# AVRKernel.net
KiCad netlist of a schematic drawn in Altium Designer
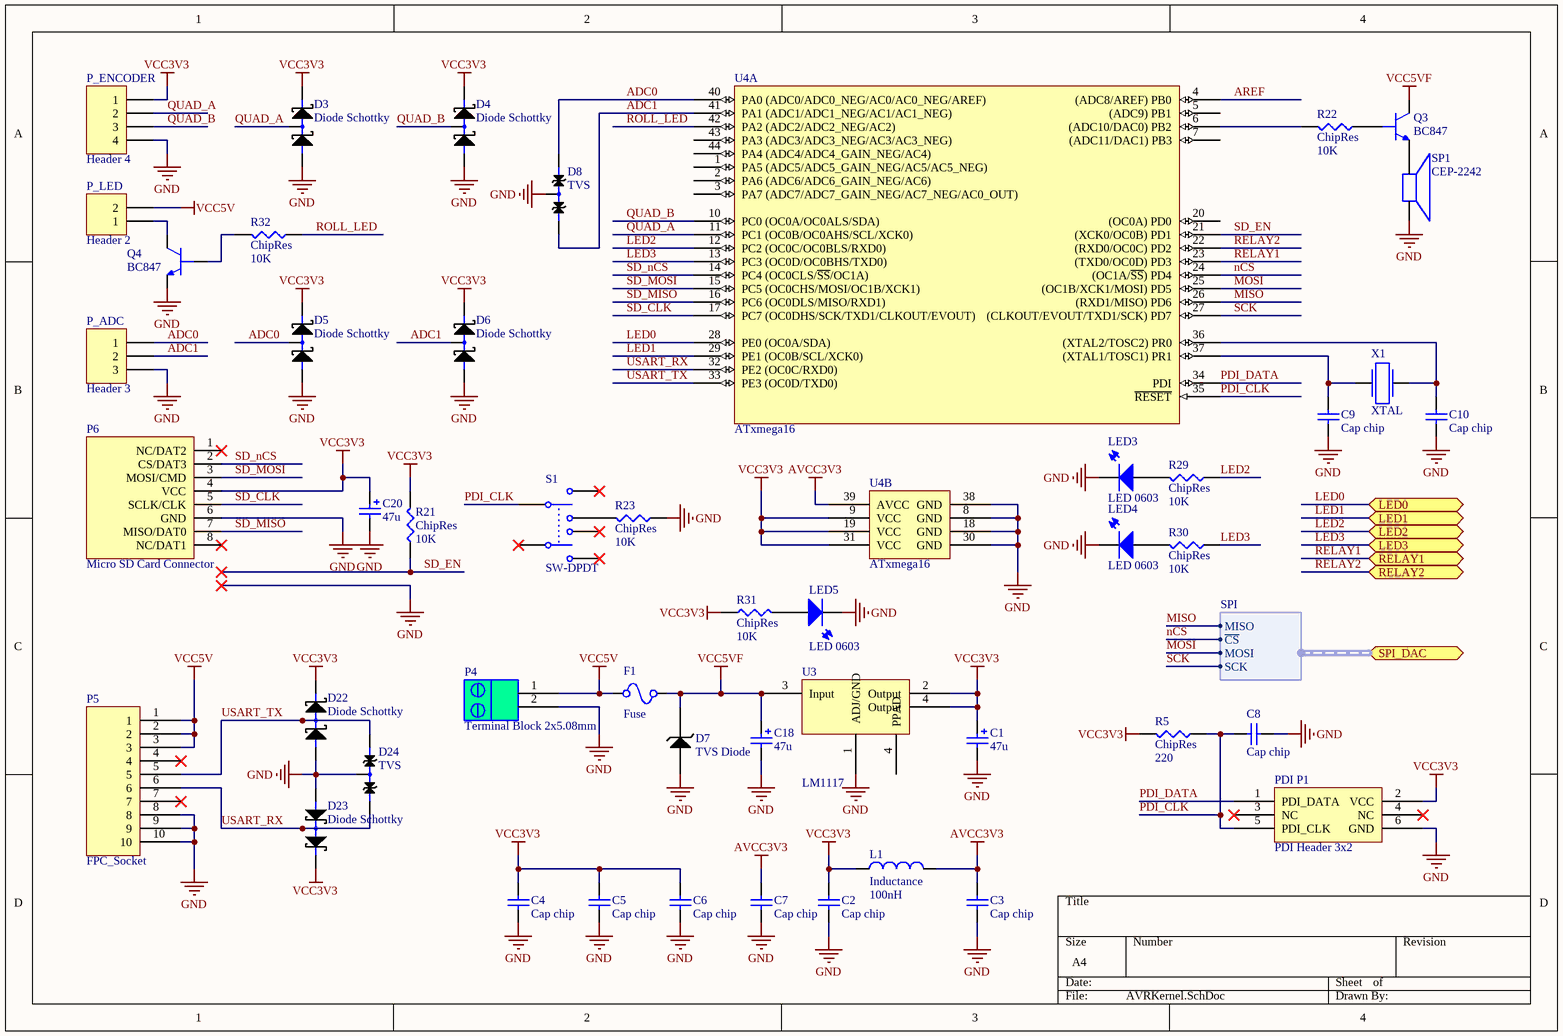
[diagram p0: AVRKernel.SchDoc]

(export (version "E")
  (design (tool "Eeschema 10.0.6"))
  (components
    (comp (ref "C1")
      (value "47u")
      (footprint "CAPC7343")
      (description "Polarized Capacitor (Radial)")
      (fields (field (name "Comment") "Cap Pol SMD"))
      (libsource (lib "Common Devices") (part "Cap Pol Chip"))
    )
    (comp (ref "C2")
      (value "Cap chip")
      (footprint "CAPC3216")
      (description "Chip Capacitor")
      (fields (field (name "PUBLISHER") "Altium Limited"))
      (libsource (lib "Common Devices") (part "Cap chip"))
    )
    (comp (ref "C3")
      (value "Cap chip")
      (footprint "CAPC3216")
      (description "Chip Capacitor")
      (fields (field (name "PUBLISHER") "Altium Limited"))
      (libsource (lib "Common Devices") (part "Cap chip"))
    )
    (comp (ref "C4")
      (value "Cap chip")
      (footprint "CAPC3216")
      (description "Chip Capacitor")
      (fields (field (name "PUBLISHER") "Altium Limited"))
      (libsource (lib "Common Devices") (part "Cap chip"))
    )
    (comp (ref "C5")
      (value "Cap chip")
      (footprint "CAPC3216")
      (description "Chip Capacitor")
      (fields (field (name "PUBLISHER") "Altium Limited"))
      (libsource (lib "Common Devices") (part "Cap chip"))
    )
    (comp (ref "C6")
      (value "Cap chip")
      (footprint "CAPC3216")
      (description "Chip Capacitor")
      (fields (field (name "PUBLISHER") "Altium Limited"))
      (libsource (lib "Common Devices") (part "Cap chip"))
    )
    (comp (ref "C7")
      (value "Cap chip")
      (footprint "CAPC3216")
      (description "Chip Capacitor")
      (fields (field (name "PUBLISHER") "Altium Limited"))
      (libsource (lib "Common Devices") (part "Cap chip"))
    )
    (comp (ref "C8")
      (value "Cap chip")
      (footprint "CAPC3216")
      (description "Chip Capacitor")
      (fields (field (name "PUBLISHER") "Altium Limited"))
      (libsource (lib "Common Devices") (part "Cap chip"))
    )
    (comp (ref "C9")
      (value "Cap chip")
      (footprint "CAPC3216")
      (description "Chip Capacitor")
      (fields (field (name "PUBLISHER") "Altium Limited"))
      (libsource (lib "Common Devices") (part "Cap chip"))
    )
    (comp (ref "C10")
      (value "Cap chip")
      (footprint "CAPC3216")
      (description "Chip Capacitor")
      (fields (field (name "PUBLISHER") "Altium Limited"))
      (libsource (lib "Common Devices") (part "Cap chip"))
    )
    (comp (ref "C18")
      (value "47u")
      (footprint "CAPC7343")
      (description "Polarized Capacitor (Radial)")
      (fields (field (name "Comment") "Cap Pol SMD"))
      (libsource (lib "Common Devices") (part "Cap Pol Chip"))
    )
    (comp (ref "C20")
      (value "47u")
      (footprint "CAPC7343")
      (description "Polarized Capacitor (Radial)")
      (fields (field (name "Comment") "Cap Pol SMD"))
      (libsource (lib "Common Devices") (part "Cap Pol Chip"))
    )
    (comp (ref "D3")
      (value "Diode Schottky")
      (footprint "SOT23")
      (description "2-Diode Schottky")
      (libsource (lib "Protection") (part "Schottky Diode"))
    )
    (comp (ref "D4")
      (value "Diode Schottky")
      (footprint "SOT23")
      (description "2-Diode Schottky")
      (libsource (lib "Protection") (part "Schottky Diode"))
    )
    (comp (ref "D5")
      (value "Diode Schottky")
      (footprint "SOT23")
      (description "2-Diode Schottky")
      (libsource (lib "Protection") (part "Schottky Diode"))
    )
    (comp (ref "D6")
      (value "Diode Schottky")
      (footprint "SOT23")
      (description "2-Diode Schottky")
      (libsource (lib "Protection") (part "Schottky Diode"))
    )
    (comp (ref "D7")
      (value "TVS Diode")
      (footprint "DO-214AS")
      (libsource (lib "Protection") (part "TVS Diode SMA"))
    )
    (comp (ref "D8")
      (value "TVS")
      (footprint "SOT23")
      (description "Dual bidirectional voltage supresor")
      (libsource (lib "Protection") (part "TVS Diode"))
    )
    (comp (ref "D22")
      (value "Diode Schottky")
      (footprint "SOT23")
      (description "2-Diode Schottky")
      (libsource (lib "Protection") (part "Schottky Diode"))
    )
    (comp (ref "D23")
      (value "Diode Schottky")
      (footprint "SOT23")
      (description "2-Diode Schottky")
      (libsource (lib "") (part "Schottky Diode_1"))
    )
    (comp (ref "D24")
      (value "TVS")
      (footprint "SOT23")
      (description "Dual bidirectional voltage supresor")
      (libsource (lib "Protection") (part "TVS Diode"))
    )
    (comp (ref "F1")
      (value "Fuse")
      (footprint "PTC1812")
      (description "Fuse PTC 1812 Thermoresistor")
      (libsource (lib "Protection") (part "Fuse PTC1812"))
    )
    (comp (ref "L1")
      (value "Inductance")
      (footprint "CM45")
      (fields (field (name "ALTIUM_VALUE") "100nH"))
      (libsource (lib "Common Devices") (part "ChipInductance"))
    )
    (comp (ref "LED3") (value "LED 0603") (footprint "LED 0603") (libsource (lib "LEDs") (part "LED0603")))
    (comp (ref "LED4") (value "LED 0603") (footprint "LED 0603") (libsource (lib "LEDs") (part "LED0603")))
    (comp (ref "LED5") (value "LED 0603") (footprint "LED 0603") (libsource (lib "LEDs") (part "LED0603")))
    (comp (ref "P4")
      (value "Terminal Block 2x5.08mm")
      (footprint "Socket 2x5.08")
      (description "Terminal Block Socket Right Angle 2x5.08mm 2 Wall")
      (libsource (lib "IndustrialConnectors") (part "Socket_2x5.08_RA_2Wall"))
    )
    (comp (ref "P5")
      (value "FPC_Socket")
      (footprint "Molex FPC/FFC 10pin")
      (libsource (lib "RibbonConnector") (part "FPC_Socket"))
    )
    (comp (ref "P6")
      (value "Micro SD Card Connector")
      (footprint "WR-CRD SD Micro")
      (libsource (lib "Connectors") (part "MicroSDHeader8"))
    )
    (comp (ref "PDI P1")
      (value "PDI Header 3x2")
      (footprint "Header 3x2")
      (description "PDI Interface connector")
      (libsource (lib "IndustrialConnectors") (part "PDI Header 3x2"))
    )
    (comp (ref "P_ADC")
      (value "Header 3")
      (footprint "HDR1X3")
      (description "Header, 3-Pin")
      (fields (field (name "PUBLISHER") "Altium Limited"))
      (libsource (lib "Miscellaneous Connectors") (part "Header 3"))
    )
    (comp (ref "P_ENCODER")
      (value "Header 4")
      (footprint "HDR1X4")
      (description "Header, 4-Pin")
      (fields (field (name "PUBLISHER") "Altium Limited"))
      (libsource (lib "Miscellaneous Connectors") (part "Header 4"))
    )
    (comp (ref "P_LED")
      (value "Header 2")
      (footprint "HDR1X2")
      (description "Header, 2-Pin")
      (fields (field (name "PUBLISHER") "Altium Limited"))
      (libsource (lib "Miscellaneous Connectors") (part "Header 2"))
    )
    (comp (ref "Q3")
      (value "BC847")
      (footprint "SOT23")
      (description "NPN transistor")
      (libsource (lib "BJT") (part "BC847"))
    )
    (comp (ref "Q4")
      (value "BC847")
      (footprint "SOT23")
      (description "NPN transistor")
      (libsource (lib "BJT") (part "BC847"))
    )
    (comp (ref "R5")
      (value "ChipRes")
      (footprint "RES0805")
      (description "Chip resistor")
      (fields (field (name "ALTIUM_VALUE") "220"))
      (libsource (lib "Common Devices") (part "ChipRes"))
    )
    (comp (ref "R21")
      (value "ChipRes")
      (footprint "RES0805")
      (description "Chip resistor")
      (fields (field (name "ALTIUM_VALUE") "10K"))
      (libsource (lib "Common Devices") (part "ChipRes"))
    )
    (comp (ref "R22")
      (value "ChipRes")
      (footprint "RES0805")
      (description "Chip resistor")
      (fields (field (name "ALTIUM_VALUE") "10K"))
      (libsource (lib "Common Devices") (part "ChipRes"))
    )
    (comp (ref "R23")
      (value "ChipRes")
      (footprint "RES0805")
      (description "Chip resistor")
      (fields (field (name "ALTIUM_VALUE") "10K"))
      (libsource (lib "Common Devices") (part "ChipRes"))
    )
    (comp (ref "R29")
      (value "ChipRes")
      (footprint "RES0805")
      (description "Chip resistor")
      (fields (field (name "ALTIUM_VALUE") "10K"))
      (libsource (lib "Common Devices") (part "ChipRes"))
    )
    (comp (ref "R30")
      (value "ChipRes")
      (footprint "RES0805")
      (description "Chip resistor")
      (fields (field (name "ALTIUM_VALUE") "10K"))
      (libsource (lib "Common Devices") (part "ChipRes"))
    )
    (comp (ref "R31")
      (value "ChipRes")
      (footprint "RES0805")
      (description "Chip resistor")
      (fields (field (name "ALTIUM_VALUE") "10K"))
      (libsource (lib "Common Devices") (part "ChipRes"))
    )
    (comp (ref "R32")
      (value "ChipRes")
      (footprint "RES0805")
      (description "Chip resistor")
      (fields (field (name "ALTIUM_VALUE") "10K"))
      (libsource (lib "Common Devices") (part "ChipRes"))
    )
    (comp (ref "S1")
      (value "SW-DPDT")
      (footprint "DPDT-6")
      (description "Double-Pole, Double-Throw Switch")
      (fields (field (name "PUBLISHER") "Altium Limited"))
      (libsource (lib "Miscellaneous Devices") (part "SW-DPDT"))
    )
    (comp (ref "SP1")
      (value "CEP-2242")
      (footprint "Buzzer")
      (description "Buzzer")
      (libsource (lib "Buzzer") (part "Buzzer CEP-2242"))
    )
    (comp (ref "U3")
      (value "LM1117")
      (footprint "SOT223-4M")
      (description "Power Mgt Voltage Regulator")
      (libsource (lib "TI Step Motor Driver") (part "LM1117"))
    )
    (comp (ref "U4")
      (value "ATxmega16")
      (footprint "44A_L")
      (description "8-Bit AVR XMEGA Microcontroller with 16K Bytes of In-System Programmable Flash Memory")
      (libsource (lib "Atmel Xmega microcontrollers") (part "ATxmega16"))
    )
    (comp (ref "X1")
      (value "XTAL")
      (footprint "BCY-W2/E4.7")
      (description "Quartz crystall oscillator")
      (libsource (lib "Common Devices") (part "Crystall oscillator"))
    )
  )
  (nets
    (net (code "2") (name "/ADC0") (class "Default")
      (node (ref "D5") (pin "3") (pinfunction "3_3") (pintype "passive"))
      (node (ref "D8") (pin "1") (pinfunction "1_1") (pintype "passive"))
      (node (ref "P_ADC") (pin "1") (pinfunction "1_1") (pintype "passive"))
      (node (ref "U4") (pin "40") (pinfunction "PA0_(ADC0/ADC0_NEG/AC0/AC0_NEG/AREF)_40") (pintype "bidirectional"))
    )
    (net (code "3") (name "/ADC1") (class "Default")
      (node (ref "D6") (pin "3") (pinfunction "3_3") (pintype "passive"))
      (node (ref "D8") (pin "2") (pinfunction "2_2") (pintype "passive"))
      (node (ref "P_ADC") (pin "2") (pinfunction "2_2") (pintype "passive"))
      (node (ref "U4") (pin "41") (pinfunction "PA1_(ADC1/ADC1_NEG/AC1/AC1_NEG)_41") (pintype "bidirectional"))
    )
    (net (code "4") (name "/AREF") (class "Default")
      (node (ref "U4") (pin "4") (pinfunction "(ADC8/AREF)_PB0_4") (pintype "bidirectional"))
    )
    (net (code "5") (name "/LED0") (class "Default")
      (node (ref "U4") (pin "28") (pinfunction "PE0_(OC0A/SDA)_28") (pintype "bidirectional"))
    )
    (net (code "6") (name "/LED1") (class "Default")
      (node (ref "U4") (pin "29") (pinfunction "PE1_(OC0B/SCL/XCK0)_29") (pintype "bidirectional"))
    )
    (net (code "7") (name "/LED2") (class "Default")
      (node (ref "R29") (pin "1") (pintype "passive"))
      (node (ref "U4") (pin "12") (pinfunction "PC2_(OC0C/OC0BLS/RXD0)_12") (pintype "bidirectional"))
    )
    (net (code "8") (name "/LED3") (class "Default")
      (node (ref "R30") (pin "1") (pintype "passive"))
      (node (ref "U4") (pin "13") (pinfunction "PC3_(OC0D/OC0BHS/TXD0)_13") (pintype "bidirectional"))
    )
    (net (code "9") (name "/MISO") (class "Default")
      (node (ref "U4") (pin "26") (pinfunction "(RXD1/MISO)_PD6_26") (pintype "bidirectional"))
    )
    (net (code "10") (name "/MOSI") (class "Default")
      (node (ref "U4") (pin "25") (pinfunction "(OC1B/XCK1/MOSI)_PD5_25") (pintype "bidirectional"))
    )
    (net (code "11") (name "/PDI_CLK") (class "Default")
      (node (ref "C8") (pin "2") (pinfunction "2_2") (pintype "passive"))
      (node (ref "PDI P1") (pin "5") (pinfunction "PDI_CLK_5") (pintype "passive"))
      (node (ref "R5") (pin "1") (pintype "passive"))
      (node (ref "S1") (pin "1") (pinfunction "1_1") (pintype "passive"))
      (node (ref "U4") (pin "35") (pinfunction "~{RESET}_35") (pintype "input"))
    )
    (net (code "12") (name "/PDI_DATA") (class "Default")
      (node (ref "PDI P1") (pin "1") (pinfunction "PDI_DATA_1") (pintype "passive"))
      (node (ref "U4") (pin "34") (pinfunction "PDI_34") (pintype "bidirectional"))
    )
    (net (code "13") (name "/QUAD_A") (class "Default")
      (node (ref "D3") (pin "3") (pinfunction "3_3") (pintype "passive"))
      (node (ref "P_ENCODER") (pin "2") (pinfunction "2_2") (pintype "passive"))
      (node (ref "U4") (pin "11") (pinfunction "PC1_(OC0B/OC0AHS/SCL/XCK0)_11") (pintype "bidirectional"))
    )
    (net (code "14") (name "/QUAD_B") (class "Default")
      (node (ref "D4") (pin "3") (pinfunction "3_3") (pintype "passive"))
      (node (ref "P_ENCODER") (pin "3") (pinfunction "3_3") (pintype "passive"))
      (node (ref "U4") (pin "10") (pinfunction "PC0_(OC0A/OC0ALS/SDA)_10") (pintype "bidirectional"))
    )
    (net (code "15") (name "/RELAY1") (class "Default")
      (node (ref "U4") (pin "23") (pinfunction "(TXD0/OC0D)_PD3_23") (pintype "bidirectional"))
    )
    (net (code "16") (name "/RELAY2") (class "Default")
      (node (ref "U4") (pin "22") (pinfunction "(RXD0/OC0C)_PD2_22") (pintype "bidirectional"))
    )
    (net (code "17") (name "/ROLL_LED") (class "Default")
      (node (ref "R32") (pin "1") (pintype "passive"))
      (node (ref "U4") (pin "42") (pinfunction "PA2_(ADC2/ADC2_NEG/AC2)_42") (pintype "bidirectional"))
    )
    (net (code "18") (name "/SCK") (class "Default")
      (node (ref "U4") (pin "27") (pinfunction "(CLKOUT/EVOUT/TXD1/SCK)_PD7_27") (pintype "bidirectional"))
    )
    (net (code "19") (name "/SD_CLK") (class "Default")
      (node (ref "P6") (pin "5") (pinfunction "SCLK/CLK_5") (pintype "passive"))
      (node (ref "U4") (pin "17") (pinfunction "PC7_(OC0DHS/SCK/TXD1/CLKOUT/EVOUT)_17") (pintype "bidirectional"))
    )
    (net (code "20") (name "/SD_EN") (class "Default")
      (node (ref "R21") (pin "1") (pintype "passive"))
      (node (ref "U4") (pin "21") (pinfunction "(XCK0/OC0B)_PD1_21") (pintype "bidirectional"))
    )
    (net (code "21") (name "/SD_MISO") (class "Default")
      (node (ref "P6") (pin "7") (pinfunction "MISO/DAT0_7") (pintype "passive"))
      (node (ref "U4") (pin "16") (pinfunction "PC6_(OC0DLS/MISO/RXD1)_16") (pintype "bidirectional"))
    )
    (net (code "22") (name "/SD_MOSI") (class "Default")
      (node (ref "P6") (pin "3") (pinfunction "MOSI/CMD_3") (pintype "passive"))
      (node (ref "U4") (pin "15") (pinfunction "PC5_(OC0CHS/MOSI/OC1B/XCK1)_15") (pintype "bidirectional"))
    )
    (net (code "23") (name "/SD_nCS") (class "Default")
      (node (ref "P6") (pin "2") (pinfunction "CS/DAT3_2") (pintype "passive"))
      (node (ref "U4") (pin "14") (pinfunction "PC4_(OC0CLS/~{SS}/OC1A)_14") (pintype "bidirectional"))
    )
    (net (code "24") (name "/USART_RX") (class "Default")
      (node (ref "D23") (pin "3") (pinfunction "3_3") (pintype "passive"))
      (node (ref "D24") (pin "2") (pinfunction "2_2") (pintype "passive"))
      (node (ref "P5") (pin "6") (pinfunction "6_6") (pintype "passive"))
      (node (ref "U4") (pin "32") (pinfunction "PE2_(OC0C/RXD0)_32") (pintype "bidirectional"))
    )
    (net (code "25") (name "/USART_TX") (class "Default")
      (node (ref "D22") (pin "3") (pinfunction "3_3") (pintype "passive"))
      (node (ref "D24") (pin "1") (pinfunction "1_1") (pintype "passive"))
      (node (ref "P5") (pin "5") (pinfunction "5_5") (pintype "passive"))
      (node (ref "U4") (pin "33") (pinfunction "PE3_(OC0D/TXD0)_33") (pintype "bidirectional"))
    )
    (net (code "26") (name "/nCS") (class "Default")
      (node (ref "U4") (pin "24") (pinfunction "(OC1A/~{SS})_PD4_24") (pintype "bidirectional"))
    )
    (net (code "28") (name "AVCC3V3") (class "Default")
      (node (ref "C3") (pin "1") (pinfunction "1_1") (pintype "passive"))
      (node (ref "C7") (pin "2") (pinfunction "2_2") (pintype "passive"))
      (node (ref "L1") (pin "1") (pintype "passive"))
      (node (ref "U4") (pin "39") (pinfunction "AVCC_39") (pintype "passive"))
    )
    (net (code "29") (name "GND") (class "Default")
      (node (ref "C1") (pin "2") (pinfunction "2_2") (pintype "passive"))
      (node (ref "C10") (pin "1") (pinfunction "1_1") (pintype "passive"))
      (node (ref "C18") (pin "2") (pinfunction "2_2") (pintype "passive"))
      (node (ref "C2") (pin "2") (pinfunction "2_2") (pintype "passive"))
      (node (ref "C20") (pin "2") (pinfunction "2_2") (pintype "passive"))
      (node (ref "C3") (pin "2") (pinfunction "2_2") (pintype "passive"))
      (node (ref "C4") (pin "1") (pinfunction "1_1") (pintype "passive"))
      (node (ref "C5") (pin "1") (pinfunction "1_1") (pintype "passive"))
      (node (ref "C6") (pin "1") (pinfunction "1_1") (pintype "passive"))
      (node (ref "C7") (pin "1") (pinfunction "1_1") (pintype "passive"))
      (node (ref "C8") (pin "1") (pinfunction "1_1") (pintype "passive"))
      (node (ref "C9") (pin "1") (pinfunction "1_1") (pintype "passive"))
      (node (ref "D22") (pin "1") (pinfunction "1_1") (pintype "passive"))
      (node (ref "D23") (pin "1") (pinfunction "1_1") (pintype "passive"))
      (node (ref "D24") (pin "3") (pinfunction "3_3") (pintype "passive"))
      (node (ref "D3") (pin "1") (pinfunction "1_1") (pintype "passive"))
      (node (ref "D4") (pin "1") (pinfunction "1_1") (pintype "passive"))
      (node (ref "D5") (pin "1") (pinfunction "1_1") (pintype "passive"))
      (node (ref "D6") (pin "1") (pinfunction "1_1") (pintype "passive"))
      (node (ref "D7") (pin "2") (pinfunction "2_2") (pintype "passive"))
      (node (ref "D8") (pin "3") (pinfunction "3_3") (pintype "passive"))
      (node (ref "LED3") (pin "1") (pinfunction "1_1") (pintype "passive"))
      (node (ref "LED4") (pin "1") (pinfunction "1_1") (pintype "passive"))
      (node (ref "LED5") (pin "1") (pinfunction "1_1") (pintype "passive"))
      (node (ref "P4") (pin "2") (pintype "passive"))
      (node (ref "P5") (pin "10") (pinfunction "10_10") (pintype "passive"))
      (node (ref "P5") (pin "8") (pinfunction "8_8") (pintype "passive"))
      (node (ref "P5") (pin "9") (pinfunction "9_9") (pintype "passive"))
      (node (ref "P6") (pin "6") (pinfunction "GND_6") (pintype "passive"))
      (node (ref "PDI P1") (pin "6") (pinfunction "GND_6") (pintype "passive"))
      (node (ref "P_ADC") (pin "3") (pinfunction "3_3") (pintype "passive"))
      (node (ref "P_ENCODER") (pin "4") (pinfunction "4_4") (pintype "passive"))
      (node (ref "Q4") (pin "2") (pinfunction "2_2") (pintype "passive"))
      (node (ref "R23") (pin "1") (pintype "passive"))
      (node (ref "SP1") (pin "2") (pinfunction "2_2") (pintype "passive"))
      (node (ref "U3") (pin "1") (pinfunction "ADJ/GND_1") (pintype "power_in"))
      (node (ref "U4") (pin "18") (pinfunction "GND_18") (pintype "passive"))
      (node (ref "U4") (pin "30") (pinfunction "GND_30") (pintype "passive"))
      (node (ref "U4") (pin "38") (pinfunction "GND_38") (pintype "passive"))
      (node (ref "U4") (pin "8") (pinfunction "GND_8") (pintype "passive"))
    )
    (net (code "30") (name "Net-(LED3-Pad2)") (class "Default")
      (node (ref "LED3") (pin "2") (pinfunction "2_2") (pintype "passive"))
      (node (ref "R29") (pin "2") (pintype "passive"))
    )
    (net (code "31") (name "Net-(LED4-Pad2)") (class "Default")
      (node (ref "LED4") (pin "2") (pinfunction "2_2") (pintype "passive"))
      (node (ref "R30") (pin "2") (pintype "passive"))
    )
    (net (code "32") (name "Net-(LED5-Pad2)") (class "Default")
      (node (ref "LED5") (pin "2") (pinfunction "2_2") (pintype "passive"))
      (node (ref "R31") (pin "2") (pintype "passive"))
    )
    (net (code "33") (name "Net-(P_LED-Pad1)") (class "Default")
      (node (ref "P_LED") (pin "1") (pinfunction "1_1") (pintype "passive"))
      (node (ref "Q4") (pin "3") (pinfunction "3_3") (pintype "passive"))
    )
    (net (code "34") (name "Net-(Q3-Pad1)") (class "Default")
      (node (ref "Q3") (pin "1") (pinfunction "1_1") (pintype "passive"))
      (node (ref "R22") (pin "1") (pintype "passive"))
    )
    (net (code "35") (name "Net-(Q3-Pad2)") (class "Default")
      (node (ref "Q3") (pin "2") (pinfunction "2_2") (pintype "passive"))
      (node (ref "SP1") (pin "1") (pinfunction "1_1") (pintype "passive"))
    )
    (net (code "36") (name "Net-(Q4-Pad1)") (class "Default")
      (node (ref "Q4") (pin "1") (pinfunction "1_1") (pintype "passive"))
      (node (ref "R32") (pin "2") (pintype "passive"))
    )
    (net (code "37") (name "Net-(R23-Pad2)") (class "Default")
      (node (ref "R23") (pin "2") (pintype "passive"))
      (node (ref "S1") (pin "3") (pinfunction "3_3") (pintype "passive"))
    )
    (net (code "38") (name "Net-(U4A-(ADC10{slash}DAC0)_PB2)") (class "Default")
      (node (ref "R22") (pin "2") (pintype "passive"))
      (node (ref "U4") (pin "6") (pinfunction "(ADC10/DAC0)_PB2_6") (pintype "bidirectional"))
    )
    (net (code "39") (name "Net-(U4A-(XTAL1{slash}TOSC1)_PR1)") (class "Default")
      (node (ref "C9") (pin "2") (pinfunction "2_2") (pintype "passive"))
      (node (ref "U4") (pin "37") (pinfunction "(XTAL1/TOSC1)_PR1_37") (pintype "bidirectional"))
      (node (ref "X1") (pin "1") (pinfunction "1_1") (pintype "passive"))
    )
    (net (code "40") (name "Net-(U4A-(XTAL2{slash}TOSC2)_PR0)") (class "Default")
      (node (ref "C10") (pin "2") (pinfunction "2_2") (pintype "passive"))
      (node (ref "U4") (pin "36") (pinfunction "(XTAL2/TOSC2)_PR0_36") (pintype "bidirectional"))
      (node (ref "X1") (pin "2") (pinfunction "2_2") (pintype "passive"))
    )
    (net (code "41") (name "VCC3V3") (class "Default")
      (node (ref "C1") (pin "1") (pinfunction "1_1") (pintype "passive"))
      (node (ref "C2") (pin "1") (pinfunction "1_1") (pintype "passive"))
      (node (ref "C20") (pin "1") (pinfunction "1_1") (pintype "passive"))
      (node (ref "C4") (pin "2") (pinfunction "2_2") (pintype "passive"))
      (node (ref "C5") (pin "2") (pinfunction "2_2") (pintype "passive"))
      (node (ref "C6") (pin "2") (pinfunction "2_2") (pintype "passive"))
      (node (ref "D22") (pin "2") (pinfunction "2_2") (pintype "passive"))
      (node (ref "D23") (pin "2") (pinfunction "2_2") (pintype "passive"))
      (node (ref "D3") (pin "2") (pinfunction "2_2") (pintype "passive"))
      (node (ref "D4") (pin "2") (pinfunction "2_2") (pintype "passive"))
      (node (ref "D5") (pin "2") (pinfunction "2_2") (pintype "passive"))
      (node (ref "D6") (pin "2") (pinfunction "2_2") (pintype "passive"))
      (node (ref "L1") (pin "2") (pintype "passive"))
      (node (ref "P6") (pin "4") (pinfunction "VCC_4") (pintype "passive"))
      (node (ref "PDI P1") (pin "2") (pinfunction "VCC_2") (pintype "passive"))
      (node (ref "P_ENCODER") (pin "1") (pinfunction "1_1") (pintype "passive"))
      (node (ref "R21") (pin "2") (pintype "passive"))
      (node (ref "R31") (pin "1") (pintype "passive"))
      (node (ref "R5") (pin "2") (pintype "passive"))
      (node (ref "U3") (pin "2") (pinfunction "Output_2") (pintype "power_in"))
      (node (ref "U3") (pin "4") (pinfunction "Output_4") (pintype "power_in"))
      (node (ref "U4") (pin "19") (pinfunction "VCC_19") (pintype "passive"))
      (node (ref "U4") (pin "31") (pinfunction "VCC_31") (pintype "passive"))
      (node (ref "U4") (pin "9") (pinfunction "VCC_9") (pintype "passive"))
    )
    (net (code "42") (name "VCC5V") (class "Default")
      (node (ref "F1") (pin "1") (pinfunction "1_1") (pintype "passive"))
      (node (ref "P4") (pin "1") (pintype "passive"))
      (node (ref "P5") (pin "1") (pinfunction "1_1") (pintype "passive"))
      (node (ref "P5") (pin "2") (pinfunction "2_2") (pintype "passive"))
      (node (ref "P5") (pin "3") (pinfunction "3_3") (pintype "passive"))
      (node (ref "P_LED") (pin "2") (pinfunction "2_2") (pintype "passive"))
    )
    (net (code "43") (name "VCC5VF") (class "Default")
      (node (ref "C18") (pin "1") (pinfunction "1_1") (pintype "passive"))
      (node (ref "D7") (pin "1") (pinfunction "1_1") (pintype "passive"))
      (node (ref "F1") (pin "2") (pinfunction "2_2") (pintype "passive"))
      (node (ref "Q3") (pin "3") (pinfunction "3_3") (pintype "passive"))
      (node (ref "U3") (pin "3") (pinfunction "Input_3") (pintype "power_in"))
    )
    (net (code "44") (name "unconnected-(P5-Pad4)") (class "Default")
      (node (ref "P5") (pin "4") (pinfunction "4_4") (pintype "passive+no_connect"))
    )
    (net (code "45") (name "unconnected-(P5-Pad7)") (class "Default")
      (node (ref "P5") (pin "7") (pinfunction "7_7") (pintype "passive+no_connect"))
    )
    (net (code "46") (name "unconnected-(P6-NC{slash}DAT1-Pad8)") (class "Default")
      (node (ref "P6") (pin "8") (pinfunction "NC/DAT1_8") (pintype "passive+no_connect"))
    )
    (net (code "47") (name "unconnected-(P6-NC{slash}DAT2-Pad1)") (class "Default")
      (node (ref "P6") (pin "1") (pinfunction "NC/DAT2_1") (pintype "passive+no_connect"))
    )
    (net (code "48") (name "unconnected-(PDI P1-NC-Pad3)") (class "Default")
      (node (ref "PDI P1") (pin "3") (pinfunction "NC_3") (pintype "passive+no_connect"))
    )
    (net (code "49") (name "unconnected-(PDI P1-NC-Pad4)") (class "Default")
      (node (ref "PDI P1") (pin "4") (pinfunction "NC_4") (pintype "passive+no_connect"))
    )
    (net (code "50") (name "unconnected-(S1-Pad2)") (class "Default")
      (node (ref "S1") (pin "2") (pinfunction "2_2") (pintype "passive+no_connect"))
    )
    (net (code "51") (name "unconnected-(S1-Pad4)") (class "Default")
      (node (ref "S1") (pin "4") (pinfunction "4_4") (pintype "passive+no_connect"))
    )
    (net (code "52") (name "unconnected-(S1-Pad5)") (class "Default")
      (node (ref "S1") (pin "5") (pinfunction "5_5") (pintype "passive+no_connect"))
    )
    (net (code "53") (name "unconnected-(S1-Pad6)") (class "Default")
      (node (ref "S1") (pin "6") (pinfunction "6_6") (pintype "passive+no_connect"))
    )
    (net (code "54") (name "unconnected-(U3-PPAD-Pad4)") (class "Default")
      (node (ref "U3") (pin "4") (pinfunction "PPAD_4") (pintype "passive"))
    )
    (net (code "55") (name "unconnected-(U4A-(ADC9)_PB1-Pad5)") (class "Default")
      (node (ref "U4") (pin "5") (pinfunction "(ADC9)_PB1_5") (pintype "bidirectional"))
    )
    (net (code "56") (name "unconnected-(U4A-(ADC11{slash}DAC1)_PB3-Pad7)") (class "Default")
      (node (ref "U4") (pin "7") (pinfunction "(ADC11/DAC1)_PB3_7") (pintype "bidirectional"))
    )
    (net (code "57") (name "unconnected-(U4A-(OC0A)_PD0-Pad20)") (class "Default")
      (node (ref "U4") (pin "20") (pinfunction "(OC0A)_PD0_20") (pintype "bidirectional"))
    )
    (net (code "58") (name "unconnected-(U4A-PA3_(ADC3{slash}ADC3_NEG{slash}AC3{slash}AC3_NEG)-Pad43)") (class "Default")
      (node (ref "U4") (pin "43") (pinfunction "PA3_(ADC3/ADC3_NEG/AC3/AC3_NEG)_43") (pintype "bidirectional"))
    )
    (net (code "59") (name "unconnected-(U4A-PA4_(ADC4{slash}ADC4_GAIN_NEG{slash}AC4)-Pad44)") (class "Default")
      (node (ref "U4") (pin "44") (pinfunction "PA4_(ADC4/ADC4_GAIN_NEG/AC4)_44") (pintype "bidirectional"))
    )
    (net (code "60") (name "unconnected-(U4A-PA5_(ADC5{slash}ADC5_GAIN_NEG{slash}AC5{slash}AC5_NEG)-Pad1)") (class "Default")
      (node (ref "U4") (pin "1") (pinfunction "PA5_(ADC5/ADC5_GAIN_NEG/AC5/AC5_NEG)_1") (pintype "bidirectional"))
    )
    (net (code "61") (name "unconnected-(U4A-PA6_(ADC6{slash}ADC6_GAIN_NEG{slash}AC6)-Pad2)") (class "Default")
      (node (ref "U4") (pin "2") (pinfunction "PA6_(ADC6/ADC6_GAIN_NEG/AC6)_2") (pintype "bidirectional"))
    )
    (net (code "62") (name "unconnected-(U4A-PA7_(ADC7{slash}ADC7_GAIN_NEG{slash}AC7_NEG{slash}AC0_OUT)-Pad3)") (class "Default")
      (node (ref "U4") (pin "3") (pinfunction "PA7_(ADC7/ADC7_GAIN_NEG/AC7_NEG/AC0_OUT)_3") (pintype "bidirectional"))
    )
  )
)
